# GEX_Dongle.net
KiCad netlist of a schematic drawn in Altium Designer
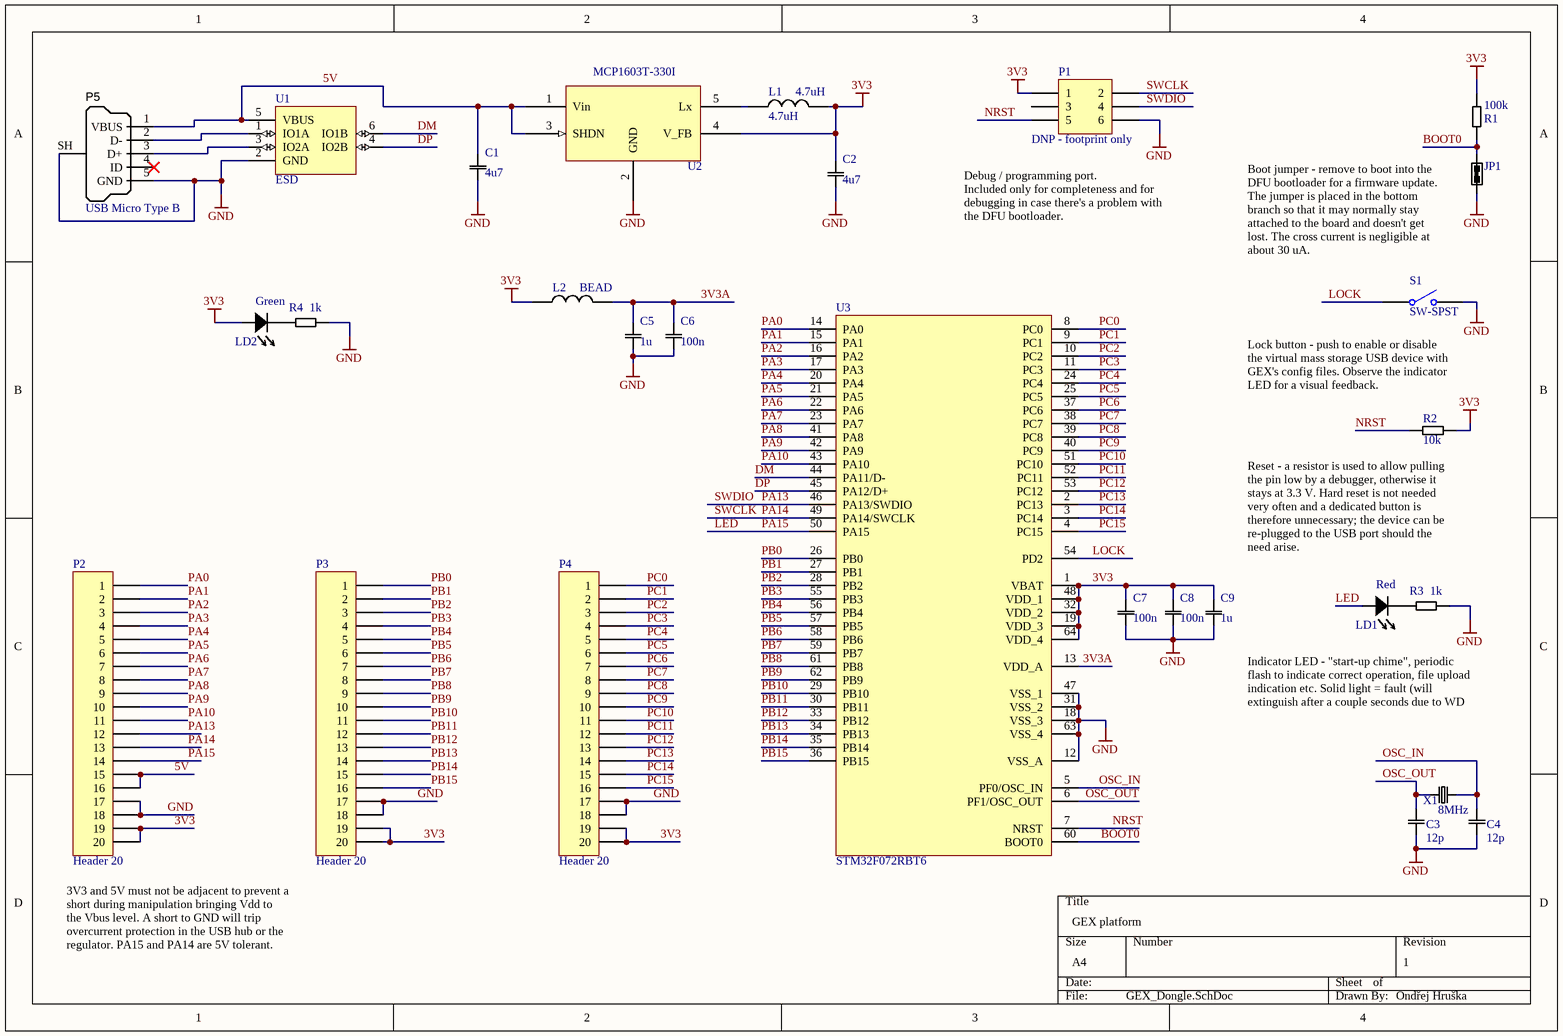
[diagram p0: GEX_Dongle.SchDoc]

(export (version "E")
  (design (tool "Eeschema 10.0.6"))
  (components
    (comp (ref "C1")
      (value "4u7")
      (footprint "ABU_standard:C1206")
      (libsource (lib "ABU_standard") (part "C"))
    )
    (comp (ref "C2")
      (value "4u7")
      (footprint "ABU_standard:C1206")
      (libsource (lib "ABU_standard") (part "C"))
    )
    (comp (ref "C3")
      (value "12p")
      (footprint "ABU_standard:C0805")
      (libsource (lib "ABU_standard") (part "C"))
    )
    (comp (ref "C4")
      (value "12p")
      (footprint "ABU_standard:C0805")
      (libsource (lib "ABU_standard") (part "C"))
    )
    (comp (ref "C5")
      (value "1u")
      (footprint "ABU_standard:C0805")
      (libsource (lib "ABU_standard") (part "C"))
    )
    (comp (ref "C6")
      (value "100n")
      (footprint "ABU_standard:C0805")
      (libsource (lib "ABU_standard") (part "C"))
    )
    (comp (ref "C7")
      (value "100n")
      (footprint "ABU_standard:C0805")
      (libsource (lib "ABU_standard") (part "C"))
    )
    (comp (ref "C8")
      (value "100n")
      (footprint "ABU_standard:C0805")
      (libsource (lib "ABU_standard") (part "C"))
    )
    (comp (ref "C9")
      (value "1u")
      (footprint "ABU_standard:C0805")
      (libsource (lib "ABU_standard") (part "C"))
    )
    (comp (ref "JP1")
      (value "JUMP")
      (footprint "Header_2_1mm")
      (libsource (lib "ABU_standard") (part "JUMP"))
    )
    (comp (ref "L1")
      (value "4.7uH")
      (footprint "L_3x3")
      (description "Inductor")
      (fields (field (name "ALTIUM_VALUE") "4.7uH") (field (name "PART NUMBER") "VLS3015ET-4R7M"))
      (libsource (lib "ABU_standard") (part "L"))
    )
    (comp (ref "L2")
      (value "BEAD")
      (footprint "R0805")
      (description "Inductor")
      (libsource (lib "ABU_standard") (part "L"))
    )
    (comp (ref "LD1") (value "Red") (footprint "LED_SMD") (libsource (lib "ABU_standard") (part "LED")))
    (comp (ref "LD2") (value "Green") (footprint "LED_SMD") (libsource (lib "ABU_standard") (part "LED")))
    (comp (ref "P1")
      (value "DNP - footprint only")
      (footprint "Header_3x2_1mm")
      (description "Header, 3-Pin, Dual row")
      (fields (field (name "PUBLISHER") "Altium Limited"))
      (libsource (lib "Miscellaneous Connectors") (part "Header 3X2"))
    )
    (comp (ref "P2")
      (value "Header 20")
      (footprint "MLW20_GEX_14")
      (description "Header, 20-Pin")
      (fields (field (name "PUBLISHER") "Altium Limited"))
      (libsource (lib "Miscellaneous Connectors") (part "Header 20"))
    )
    (comp (ref "P3")
      (value "Header 20")
      (footprint "MLW20_GEX_16")
      (description "Header, 20-Pin")
      (fields (field (name "PUBLISHER") "Altium Limited"))
      (libsource (lib "Miscellaneous Connectors") (part "Header 20"))
    )
    (comp (ref "P4")
      (value "Header 20")
      (footprint "MLW20_GEX_16")
      (description "Header, 20-Pin")
      (fields (field (name "PUBLISHER") "Altium Limited"))
      (libsource (lib "Miscellaneous Connectors") (part "Header 20"))
    )
    (comp (ref "P5")
      (value "USB Micro Type B")
      (footprint "USB_Micro-B_AFCI_10118194")
      (description "Connector SMD USB Micro Type B bottom mount, (recommended if hand soldering)")
      (fields (field (name "Comment") "USB_Micro_TypeB_Molex_105017"))
      (libsource (lib "CONN") (part "USB_Micro_TypeB_Molex_105017"))
    )
    (comp (ref "R1") (value "100k") (footprint "R0805") (libsource (lib "") (part "R_1")))
    (comp (ref "R2") (value "10k") (footprint "R0805") (libsource (lib "ABU_standard") (part "R")))
    (comp (ref "R3") (value "1k") (footprint "R0805") (libsource (lib "ABU_standard") (part "R")))
    (comp (ref "R4") (value "1k") (footprint "R0805") (libsource (lib "ABU_standard") (part "R")))
    (comp (ref "S1")
      (value "SW-SPST")
      (footprint "BTN_AJ050")
      (description "Single-Pole, Single-Throw Switch")
      (fields (field (name "PUBLISHER") "Altium Limited"))
      (libsource (lib "Miscellaneous Devices") (part "SW-SPST"))
    )
    (comp (ref "U1") (value "ESD") (footprint "SOT23-6") (libsource (lib "CUSTOM") (part "USBLC6_ESD")))
    (comp (ref "U2")
      (value "MCP1603T-330I")
      (footprint "SOT23-5")
      (libsource (lib "CUSTOM") (part "MCP1603"))
    )
    (comp (ref "U3")
      (value "STM32F072RBT6")
      (footprint "LQFP64")
      (libsource (lib "CUSTOM") (part "STM32F072RBT6"))
    )
    (comp (ref "X1")
      (value "8MHz")
      (footprint "XTAL-SMD-50-32")
      (libsource (lib "ABU_standard") (part "XTALL"))
    )
  )
  (nets
    (net (code "1") (name "/3V3A") (class "Default")
      (node (ref "C5") (pin "2") (pinfunction "2_2") (pintype "passive"))
      (node (ref "C6") (pin "2") (pinfunction "2_2") (pintype "passive"))
      (node (ref "L2") (pin "2") (pinfunction "2_2") (pintype "passive"))
      (node (ref "U3") (pin "13") (pinfunction "VDD_A_13") (pintype "power_in"))
    )
    (net (code "2") (name "/5V") (class "Default")
      (node (ref "C1") (pin "2") (pinfunction "2_2") (pintype "passive"))
      (node (ref "P2") (pin "15") (pinfunction "15_15") (pintype "passive"))
      (node (ref "P2") (pin "16") (pinfunction "16_16") (pintype "passive"))
      (node (ref "P5") (pin "1") (pinfunction "VBUS_1") (pintype "passive"))
      (node (ref "U1") (pin "5") (pinfunction "VBUS_5") (pintype "power_in"))
      (node (ref "U2") (pin "1") (pinfunction "Vin_1") (pintype "power_in"))
      (node (ref "U2") (pin "3") (pinfunction "SHDN_3") (pintype "input"))
    )
    (net (code "3") (name "/BOOT0") (class "Default")
      (node (ref "JP1") (pin "1") (pintype "passive"))
      (node (ref "R1") (pin "2") (pinfunction "2_2") (pintype "passive"))
      (node (ref "U3") (pin "60") (pinfunction "BOOT0_60") (pintype "passive"))
    )
    (net (code "4") (name "/DM") (class "Default")
      (node (ref "U1") (pin "6") (pinfunction "IO1B_6") (pintype "bidirectional"))
      (node (ref "U3") (pin "44") (pinfunction "PA11/D-_44") (pintype "passive"))
    )
    (net (code "5") (name "/DP") (class "Default")
      (node (ref "U1") (pin "4") (pinfunction "IO2B_4") (pintype "bidirectional"))
      (node (ref "U3") (pin "45") (pinfunction "PA12/D+_45") (pintype "passive"))
    )
    (net (code "6") (name "/LED") (class "Default")
      (node (ref "LD1") (pin "A") (pinfunction "A_A") (pintype "passive"))
      (node (ref "P2") (pin "14") (pinfunction "14_14") (pintype "passive"))
      (node (ref "U3") (pin "50") (pinfunction "PA15_50") (pintype "passive"))
    )
    (net (code "7") (name "/LOCK") (class "Default")
      (node (ref "S1") (pin "1") (pinfunction "COMMON_1") (pintype "passive"))
      (node (ref "U3") (pin "54") (pinfunction "PD2_54") (pintype "passive"))
    )
    (net (code "8") (name "/NRST") (class "Default")
      (node (ref "P1") (pin "5") (pinfunction "5_5") (pintype "passive"))
      (node (ref "R2") (pin "2") (pinfunction "2_2") (pintype "passive"))
      (node (ref "U3") (pin "7") (pinfunction "NRST_7") (pintype "passive"))
    )
    (net (code "9") (name "/OSC_IN") (class "Default")
      (node (ref "C4") (pin "2") (pinfunction "2_2") (pintype "passive"))
      (node (ref "U3") (pin "5") (pinfunction "PF0/OSC_IN_5") (pintype "passive"))
      (node (ref "X1") (pin "2") (pinfunction "2_2") (pintype "passive"))
    )
    (net (code "10") (name "/OSC_OUT") (class "Default")
      (node (ref "C3") (pin "2") (pinfunction "2_2") (pintype "passive"))
      (node (ref "U3") (pin "6") (pinfunction "PF1/OSC_OUT_6") (pintype "passive"))
      (node (ref "X1") (pin "1") (pinfunction "1_1") (pintype "passive"))
    )
    (net (code "11") (name "/PA0") (class "Default")
      (node (ref "P2") (pin "1") (pinfunction "1_1") (pintype "passive"))
      (node (ref "U3") (pin "14") (pinfunction "PA0_14") (pintype "passive"))
    )
    (net (code "12") (name "/PA1") (class "Default")
      (node (ref "P2") (pin "2") (pinfunction "2_2") (pintype "passive"))
      (node (ref "U3") (pin "15") (pinfunction "PA1_15") (pintype "passive"))
    )
    (net (code "13") (name "/PA2") (class "Default")
      (node (ref "P2") (pin "3") (pinfunction "3_3") (pintype "passive"))
      (node (ref "U3") (pin "16") (pinfunction "PA2_16") (pintype "passive"))
    )
    (net (code "14") (name "/PA3") (class "Default")
      (node (ref "P2") (pin "4") (pinfunction "4_4") (pintype "passive"))
      (node (ref "U3") (pin "17") (pinfunction "PA3_17") (pintype "passive"))
    )
    (net (code "15") (name "/PA4") (class "Default")
      (node (ref "P2") (pin "5") (pinfunction "5_5") (pintype "passive"))
      (node (ref "U3") (pin "20") (pinfunction "PA4_20") (pintype "passive"))
    )
    (net (code "16") (name "/PA5") (class "Default")
      (node (ref "P2") (pin "6") (pinfunction "6_6") (pintype "passive"))
      (node (ref "U3") (pin "21") (pinfunction "PA5_21") (pintype "passive"))
    )
    (net (code "17") (name "/PA6") (class "Default")
      (node (ref "P2") (pin "7") (pinfunction "7_7") (pintype "passive"))
      (node (ref "U3") (pin "22") (pinfunction "PA6_22") (pintype "passive"))
    )
    (net (code "18") (name "/PA7") (class "Default")
      (node (ref "P2") (pin "8") (pinfunction "8_8") (pintype "passive"))
      (node (ref "U3") (pin "23") (pinfunction "PA7_23") (pintype "passive"))
    )
    (net (code "19") (name "/PA8") (class "Default")
      (node (ref "P2") (pin "9") (pinfunction "9_9") (pintype "passive"))
      (node (ref "U3") (pin "41") (pinfunction "PA8_41") (pintype "passive"))
    )
    (net (code "20") (name "/PA9") (class "Default")
      (node (ref "P2") (pin "10") (pinfunction "10_10") (pintype "passive"))
      (node (ref "U3") (pin "42") (pinfunction "PA9_42") (pintype "passive"))
    )
    (net (code "21") (name "/PA10") (class "Default")
      (node (ref "P2") (pin "11") (pinfunction "11_11") (pintype "passive"))
      (node (ref "U3") (pin "43") (pinfunction "PA10_43") (pintype "passive"))
    )
    (net (code "22") (name "/PA13") (class "Default")
      (node (ref "P1") (pin "4") (pinfunction "4_4") (pintype "passive"))
      (node (ref "P2") (pin "12") (pinfunction "12_12") (pintype "passive"))
      (node (ref "U3") (pin "46") (pinfunction "PA13/SWDIO_46") (pintype "passive"))
    )
    (net (code "23") (name "/PA14") (class "Default")
      (node (ref "P1") (pin "2") (pinfunction "2_2") (pintype "passive"))
      (node (ref "P2") (pin "13") (pinfunction "13_13") (pintype "passive"))
      (node (ref "U3") (pin "49") (pinfunction "PA14/SWCLK_49") (pintype "passive"))
    )
    (net (code "24") (name "/PB0") (class "Default")
      (node (ref "P3") (pin "1") (pinfunction "1_1") (pintype "passive"))
      (node (ref "U3") (pin "26") (pinfunction "PB0_26") (pintype "passive"))
    )
    (net (code "25") (name "/PB1") (class "Default")
      (node (ref "P3") (pin "2") (pinfunction "2_2") (pintype "passive"))
      (node (ref "U3") (pin "27") (pinfunction "PB1_27") (pintype "passive"))
    )
    (net (code "26") (name "/PB2") (class "Default")
      (node (ref "P3") (pin "3") (pinfunction "3_3") (pintype "passive"))
      (node (ref "U3") (pin "28") (pinfunction "PB2_28") (pintype "passive"))
    )
    (net (code "27") (name "/PB3") (class "Default")
      (node (ref "P3") (pin "4") (pinfunction "4_4") (pintype "passive"))
      (node (ref "U3") (pin "55") (pinfunction "PB3_55") (pintype "passive"))
    )
    (net (code "28") (name "/PB4") (class "Default")
      (node (ref "P3") (pin "5") (pinfunction "5_5") (pintype "passive"))
      (node (ref "U3") (pin "56") (pinfunction "PB4_56") (pintype "passive"))
    )
    (net (code "29") (name "/PB5") (class "Default")
      (node (ref "P3") (pin "6") (pinfunction "6_6") (pintype "passive"))
      (node (ref "U3") (pin "57") (pinfunction "PB5_57") (pintype "passive"))
    )
    (net (code "30") (name "/PB6") (class "Default")
      (node (ref "P3") (pin "7") (pinfunction "7_7") (pintype "passive"))
      (node (ref "U3") (pin "58") (pinfunction "PB6_58") (pintype "passive"))
    )
    (net (code "31") (name "/PB7") (class "Default")
      (node (ref "P3") (pin "8") (pinfunction "8_8") (pintype "passive"))
      (node (ref "U3") (pin "59") (pinfunction "PB7_59") (pintype "passive"))
    )
    (net (code "32") (name "/PB8") (class "Default")
      (node (ref "P3") (pin "9") (pinfunction "9_9") (pintype "passive"))
      (node (ref "U3") (pin "61") (pinfunction "PB8_61") (pintype "passive"))
    )
    (net (code "33") (name "/PB9") (class "Default")
      (node (ref "P3") (pin "10") (pinfunction "10_10") (pintype "passive"))
      (node (ref "U3") (pin "62") (pinfunction "PB9_62") (pintype "passive"))
    )
    (net (code "34") (name "/PB10") (class "Default")
      (node (ref "P3") (pin "11") (pinfunction "11_11") (pintype "passive"))
      (node (ref "U3") (pin "29") (pinfunction "PB10_29") (pintype "passive"))
    )
    (net (code "35") (name "/PB11") (class "Default")
      (node (ref "P3") (pin "12") (pinfunction "12_12") (pintype "passive"))
      (node (ref "U3") (pin "30") (pinfunction "PB11_30") (pintype "passive"))
    )
    (net (code "36") (name "/PB12") (class "Default")
      (node (ref "P3") (pin "13") (pinfunction "13_13") (pintype "passive"))
      (node (ref "U3") (pin "33") (pinfunction "PB12_33") (pintype "passive"))
    )
    (net (code "37") (name "/PB13") (class "Default")
      (node (ref "P3") (pin "14") (pinfunction "14_14") (pintype "passive"))
      (node (ref "U3") (pin "34") (pinfunction "PB13_34") (pintype "passive"))
    )
    (net (code "38") (name "/PB14") (class "Default")
      (node (ref "P3") (pin "15") (pinfunction "15_15") (pintype "passive"))
      (node (ref "U3") (pin "35") (pinfunction "PB14_35") (pintype "passive"))
    )
    (net (code "39") (name "/PB15") (class "Default")
      (node (ref "P3") (pin "16") (pinfunction "16_16") (pintype "passive"))
      (node (ref "U3") (pin "36") (pinfunction "PB15_36") (pintype "passive"))
    )
    (net (code "40") (name "/PC0") (class "Default")
      (node (ref "P4") (pin "1") (pinfunction "1_1") (pintype "passive"))
      (node (ref "U3") (pin "8") (pinfunction "PC0_8") (pintype "passive"))
    )
    (net (code "41") (name "/PC1") (class "Default")
      (node (ref "P4") (pin "2") (pinfunction "2_2") (pintype "passive"))
      (node (ref "U3") (pin "9") (pinfunction "PC1_9") (pintype "passive"))
    )
    (net (code "42") (name "/PC2") (class "Default")
      (node (ref "P4") (pin "3") (pinfunction "3_3") (pintype "passive"))
      (node (ref "U3") (pin "10") (pinfunction "PC2_10") (pintype "passive"))
    )
    (net (code "43") (name "/PC3") (class "Default")
      (node (ref "P4") (pin "4") (pinfunction "4_4") (pintype "passive"))
      (node (ref "U3") (pin "11") (pinfunction "PC3_11") (pintype "passive"))
    )
    (net (code "44") (name "/PC4") (class "Default")
      (node (ref "P4") (pin "5") (pinfunction "5_5") (pintype "passive"))
      (node (ref "U3") (pin "24") (pinfunction "PC4_24") (pintype "passive"))
    )
    (net (code "45") (name "/PC5") (class "Default")
      (node (ref "P4") (pin "6") (pinfunction "6_6") (pintype "passive"))
      (node (ref "U3") (pin "25") (pinfunction "PC5_25") (pintype "passive"))
    )
    (net (code "46") (name "/PC6") (class "Default")
      (node (ref "P4") (pin "7") (pinfunction "7_7") (pintype "passive"))
      (node (ref "U3") (pin "37") (pinfunction "PC6_37") (pintype "passive"))
    )
    (net (code "47") (name "/PC7") (class "Default")
      (node (ref "P4") (pin "8") (pinfunction "8_8") (pintype "passive"))
      (node (ref "U3") (pin "38") (pinfunction "PC7_38") (pintype "passive"))
    )
    (net (code "48") (name "/PC8") (class "Default")
      (node (ref "P4") (pin "9") (pinfunction "9_9") (pintype "passive"))
      (node (ref "U3") (pin "39") (pinfunction "PC8_39") (pintype "passive"))
    )
    (net (code "49") (name "/PC9") (class "Default")
      (node (ref "P4") (pin "10") (pinfunction "10_10") (pintype "passive"))
      (node (ref "U3") (pin "40") (pinfunction "PC9_40") (pintype "passive"))
    )
    (net (code "50") (name "/PC10") (class "Default")
      (node (ref "P4") (pin "11") (pinfunction "11_11") (pintype "passive"))
      (node (ref "U3") (pin "51") (pinfunction "PC10_51") (pintype "passive"))
    )
    (net (code "51") (name "/PC11") (class "Default")
      (node (ref "P4") (pin "12") (pinfunction "12_12") (pintype "passive"))
      (node (ref "U3") (pin "52") (pinfunction "PC11_52") (pintype "passive"))
    )
    (net (code "52") (name "/PC12") (class "Default")
      (node (ref "P4") (pin "13") (pinfunction "13_13") (pintype "passive"))
      (node (ref "U3") (pin "53") (pinfunction "PC12_53") (pintype "passive"))
    )
    (net (code "53") (name "/PC13") (class "Default")
      (node (ref "P4") (pin "14") (pinfunction "14_14") (pintype "passive"))
      (node (ref "U3") (pin "2") (pinfunction "PC13_2") (pintype "passive"))
    )
    (net (code "54") (name "/PC14") (class "Default")
      (node (ref "P4") (pin "15") (pinfunction "15_15") (pintype "passive"))
      (node (ref "U3") (pin "3") (pinfunction "PC14_3") (pintype "passive"))
    )
    (net (code "55") (name "/PC15") (class "Default")
      (node (ref "P4") (pin "16") (pinfunction "16_16") (pintype "passive"))
      (node (ref "U3") (pin "4") (pinfunction "PC15_4") (pintype "passive"))
    )
    (net (code "56") (name "3V3") (class "Default")
      (node (ref "C2") (pin "2") (pinfunction "2_2") (pintype "passive"))
      (node (ref "C7") (pin "2") (pinfunction "2_2") (pintype "passive"))
      (node (ref "C8") (pin "2") (pinfunction "2_2") (pintype "passive"))
      (node (ref "C9") (pin "2") (pinfunction "2_2") (pintype "passive"))
      (node (ref "L1") (pin "2") (pinfunction "2_2") (pintype "passive"))
      (node (ref "L2") (pin "1") (pinfunction "1_1") (pintype "passive"))
      (node (ref "LD2") (pin "A") (pinfunction "A_A") (pintype "passive"))
      (node (ref "P1") (pin "1") (pinfunction "1_1") (pintype "passive"))
      (node (ref "P2") (pin "19") (pinfunction "19_19") (pintype "passive"))
      (node (ref "P2") (pin "20") (pinfunction "20_20") (pintype "passive"))
      (node (ref "P3") (pin "19") (pinfunction "19_19") (pintype "passive"))
      (node (ref "P3") (pin "20") (pinfunction "20_20") (pintype "passive"))
      (node (ref "P4") (pin "19") (pinfunction "19_19") (pintype "passive"))
      (node (ref "P4") (pin "20") (pinfunction "20_20") (pintype "passive"))
      (node (ref "R1") (pin "1") (pinfunction "1_1") (pintype "passive"))
      (node (ref "R2") (pin "1") (pinfunction "1_1") (pintype "passive"))
      (node (ref "U2") (pin "4") (pinfunction "V_FB_4") (pintype "passive"))
      (node (ref "U3") (pin "1") (pinfunction "VBAT_1") (pintype "passive"))
      (node (ref "U3") (pin "19") (pinfunction "VDD_3_19") (pintype "power_in"))
      (node (ref "U3") (pin "32") (pinfunction "VDD_2_32") (pintype "power_in"))
      (node (ref "U3") (pin "48") (pinfunction "VDD_1_48") (pintype "power_in"))
      (node (ref "U3") (pin "64") (pinfunction "VDD_4_64") (pintype "power_in"))
    )
    (net (code "57") (name "GND") (class "Default")
      (node (ref "C1") (pin "1") (pinfunction "1_1") (pintype "passive"))
      (node (ref "C2") (pin "1") (pinfunction "1_1") (pintype "passive"))
      (node (ref "C3") (pin "1") (pinfunction "1_1") (pintype "passive"))
      (node (ref "C4") (pin "1") (pinfunction "1_1") (pintype "passive"))
      (node (ref "C5") (pin "1") (pinfunction "1_1") (pintype "passive"))
      (node (ref "C6") (pin "1") (pinfunction "1_1") (pintype "passive"))
      (node (ref "C7") (pin "1") (pinfunction "1_1") (pintype "passive"))
      (node (ref "C8") (pin "1") (pinfunction "1_1") (pintype "passive"))
      (node (ref "C9") (pin "1") (pinfunction "1_1") (pintype "passive"))
      (node (ref "JP1") (pin "2") (pintype "passive"))
      (node (ref "P1") (pin "6") (pinfunction "6_6") (pintype "passive"))
      (node (ref "P2") (pin "17") (pinfunction "17_17") (pintype "passive"))
      (node (ref "P2") (pin "18") (pinfunction "18_18") (pintype "passive"))
      (node (ref "P3") (pin "17") (pinfunction "17_17") (pintype "passive"))
      (node (ref "P3") (pin "18") (pinfunction "18_18") (pintype "passive"))
      (node (ref "P4") (pin "17") (pinfunction "17_17") (pintype "passive"))
      (node (ref "P4") (pin "18") (pinfunction "18_18") (pintype "passive"))
      (node (ref "P5") (pin "5") (pinfunction "GND_5") (pintype "passive"))
      (node (ref "P5") (pin "SH") (pinfunction "Shell_SH") (pintype "passive"))
      (node (ref "R3") (pin "1") (pinfunction "1_1") (pintype "passive"))
      (node (ref "R4") (pin "1") (pinfunction "1_1") (pintype "passive"))
      (node (ref "S1") (pin "2") (pinfunction "NO_2") (pintype "passive"))
      (node (ref "U1") (pin "2") (pinfunction "GND_2") (pintype "power_in"))
      (node (ref "U2") (pin "2") (pinfunction "GND_2") (pintype "power_in"))
      (node (ref "U3") (pin "12") (pinfunction "VSS_A_12") (pintype "power_in"))
      (node (ref "U3") (pin "18") (pinfunction "VSS_3_18") (pintype "power_in"))
      (node (ref "U3") (pin "31") (pinfunction "VSS_2_31") (pintype "power_in"))
      (node (ref "U3") (pin "47") (pinfunction "VSS_1_47") (pintype "power_in"))
      (node (ref "U3") (pin "63") (pinfunction "VSS_4_63") (pintype "power_in"))
    )
    (net (code "58") (name "Net-(LD1-PadC)") (class "Default")
      (node (ref "LD1") (pin "C") (pinfunction "C_C") (pintype "passive"))
      (node (ref "R3") (pin "2") (pinfunction "2_2") (pintype "passive"))
    )
    (net (code "59") (name "Net-(LD2-PadC)") (class "Default")
      (node (ref "LD2") (pin "C") (pinfunction "C_C") (pintype "passive"))
      (node (ref "R4") (pin "2") (pinfunction "2_2") (pintype "passive"))
    )
    (net (code "60") (name "Net-(P5-D+)") (class "Default")
      (node (ref "P5") (pin "3") (pinfunction "D+_3") (pintype "passive"))
      (node (ref "U1") (pin "3") (pinfunction "IO2A_3") (pintype "bidirectional"))
    )
    (net (code "61") (name "Net-(P5-D-)") (class "Default")
      (node (ref "P5") (pin "2") (pinfunction "D-_2") (pintype "passive"))
      (node (ref "U1") (pin "1") (pinfunction "IO1A_1") (pintype "bidirectional"))
    )
    (net (code "62") (name "Net-(U2-Lx)") (class "Default")
      (node (ref "L1") (pin "1") (pinfunction "1_1") (pintype "passive"))
      (node (ref "U2") (pin "5") (pinfunction "Lx_5") (pintype "passive"))
    )
    (net (code "63") (name "unconnected-(P1-Pad3)") (class "Default")
      (node (ref "P1") (pin "3") (pinfunction "3_3") (pintype "passive"))
    )
    (net (code "64") (name "unconnected-(P5-ID-Pad4)") (class "Default")
      (node (ref "P5") (pin "4") (pinfunction "ID_4") (pintype "passive+no_connect"))
    )
  )
)
